# SDCARD.net
KiCad netlist of a schematic drawn in Altium Designer
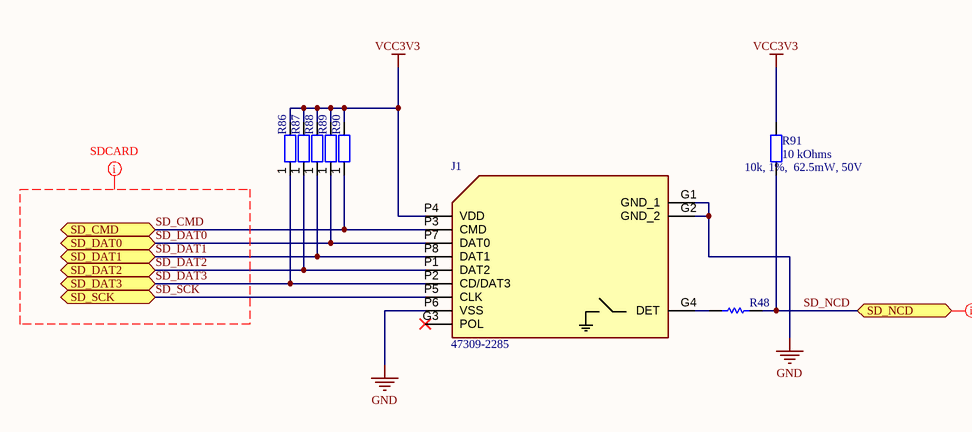
[diagram p0: SDCARD.SchDoc]

(export (version "E")
  (design (tool "Eeschema 10.0.6"))
  (components
    (comp (ref "J1")
      (value "47309-2285")
      (footprint "PCB1:473092285")
      (description "1.10mm Pitch microSD Card Header with Detect Pin Height 2.85mm Lead-Free Gold (Au) Plated 0.762")
      (fields (field (name "MOUSER PART NUMBER") "538-47309-2285") (field (name "MANUFACTURER") "Molex"))
      (libsource (lib "HamedLib") (part "47309-2285"))
    )
    (comp (ref "R48")
      (value "ERJ2RKF33R0X")
      (footprint "RESC1005X40X25LL05T05")
      (fields (field (name "MANUFACTURER") "Panasonic"))
      (libsource (lib "Altium Content Vault") (part "RES"))
    )
    (comp (ref "R86")
      (value "100 kOhms")
      (footprint "RES0402i")
      (description "0402, 100k, 1%, 62.5mW, 50V")
      (fields (field (name "PART NUMBER") "CR0402-FX-1003GLF") (field (name "VOLTAGE") "50 V"))
      (libsource (lib "AmpherLib") (part "Res_100K_1%_0402"))
    )
    (comp (ref "R87")
      (value "100 kOhms")
      (footprint "RES0402i")
      (description "0402, 100k, 1%, 62.5mW, 50V")
      (fields (field (name "PART NUMBER") "CR0402-FX-1003GLF") (field (name "VOLTAGE") "50 V"))
      (libsource (lib "AmpherLib") (part "Res_100K_1%_0402"))
    )
    (comp (ref "R88")
      (value "100 kOhms")
      (footprint "RES0402i")
      (description "0402, 100k, 1%, 62.5mW, 50V")
      (fields (field (name "PART NUMBER") "CR0402-FX-1003GLF") (field (name "VOLTAGE") "50 V"))
      (libsource (lib "AmpherLib") (part "Res_100K_1%_0402"))
    )
    (comp (ref "R89")
      (value "100 kOhms")
      (footprint "RES0402i")
      (description "0402, 100k, 1%, 62.5mW, 50V")
      (fields (field (name "PART NUMBER") "CR0402-FX-1003GLF") (field (name "VOLTAGE") "50 V"))
      (libsource (lib "AmpherLib") (part "Res_100K_1%_0402"))
    )
    (comp (ref "R90")
      (value "100 kOhms")
      (footprint "RES0402i")
      (description "0402, 100k, 1%, 62.5mW, 50V")
      (fields (field (name "PART NUMBER") "CR0402-FX-1003GLF") (field (name "VOLTAGE") "50 V"))
      (libsource (lib "AmpherLib") (part "Res_100K_1%_0402"))
    )
    (comp (ref "R91")
      (value "10 kOhms")
      (footprint "RES0402i")
      (description "0402, 10K 1%,  62.5mW, 50V")
      (fields
        (field (name "PART NUMBER") "CR0402-FX-1002GLF")
        (field (name "VOLTAGE") "50V")
        (field (name "ALTIUM_VALUE") "10k, 1%,  62.5mW, 50V")
      )
      (libsource (lib "AmpherLib") (part "Res_10k_1%_0402"))
    )
  )
  (nets
    (net (code "1") (name "/SD_CMD") (class "Default")
      (node (ref "J1") (pin "P3") (pinfunction "CMD_P3") (pintype "passive"))
      (node (ref "R90") (pin "1") (pinfunction "1_1") (pintype "passive"))
    )
    (net (code "2") (name "/SD_DAT0") (class "Default")
      (node (ref "J1") (pin "P7") (pinfunction "DAT0_P7") (pintype "passive"))
      (node (ref "R89") (pin "1") (pinfunction "1_1") (pintype "passive"))
    )
    (net (code "3") (name "/SD_DAT1") (class "Default")
      (node (ref "J1") (pin "P8") (pinfunction "DAT1_P8") (pintype "passive"))
      (node (ref "R88") (pin "1") (pinfunction "1_1") (pintype "passive"))
    )
    (net (code "4") (name "/SD_DAT2") (class "Default")
      (node (ref "J1") (pin "P1") (pinfunction "DAT2_P1") (pintype "passive"))
      (node (ref "R87") (pin "1") (pinfunction "1_1") (pintype "passive"))
    )
    (net (code "5") (name "/SD_DAT3") (class "Default")
      (node (ref "J1") (pin "P2") (pinfunction "CD/DAT3_P2") (pintype "passive"))
      (node (ref "R86") (pin "1") (pinfunction "1_1") (pintype "passive"))
    )
    (net (code "6") (name "/SD_NCD") (class "Default")
      (node (ref "R48") (pin "2") (pinfunction "2_2") (pintype "passive"))
      (node (ref "R91") (pin "1") (pinfunction "1_1") (pintype "passive"))
    )
    (net (code "7") (name "/SD_SCK") (class "Default")
      (node (ref "J1") (pin "P5") (pinfunction "CLK_P5") (pintype "passive"))
    )
    (net (code "8") (name "GND") (class "Default")
      (node (ref "J1") (pin "G1") (pinfunction "GND_1_G1") (pintype "passive"))
      (node (ref "J1") (pin "G2") (pinfunction "GND_2_G2") (pintype "passive"))
      (node (ref "J1") (pin "P6") (pinfunction "VSS_P6") (pintype "passive"))
    )
    (net (code "9") (name "Net-(J1-DET)") (class "Default")
      (node (ref "J1") (pin "G4") (pinfunction "DET_G4") (pintype "passive"))
      (node (ref "R48") (pin "1") (pinfunction "1_1") (pintype "passive"))
    )
    (net (code "10") (name "VCC3V3") (class "Default")
      (node (ref "J1") (pin "P4") (pinfunction "VDD_P4") (pintype "passive"))
      (node (ref "R86") (pin "2") (pinfunction "2_2") (pintype "passive"))
      (node (ref "R87") (pin "2") (pinfunction "2_2") (pintype "passive"))
      (node (ref "R88") (pin "2") (pinfunction "2_2") (pintype "passive"))
      (node (ref "R89") (pin "2") (pinfunction "2_2") (pintype "passive"))
      (node (ref "R90") (pin "2") (pinfunction "2_2") (pintype "passive"))
      (node (ref "R91") (pin "2") (pinfunction "2_2") (pintype "passive"))
    )
    (net (code "11") (name "unconnected-(J1-POL-PadG3)") (class "Default")
      (node (ref "J1") (pin "G3") (pinfunction "POL_G3") (pintype "passive+no_connect"))
    )
  )
)
